# UMN_HASP_2015_GPS-IMU_Board.net
KiCad netlist of a schematic drawn in EAGLE
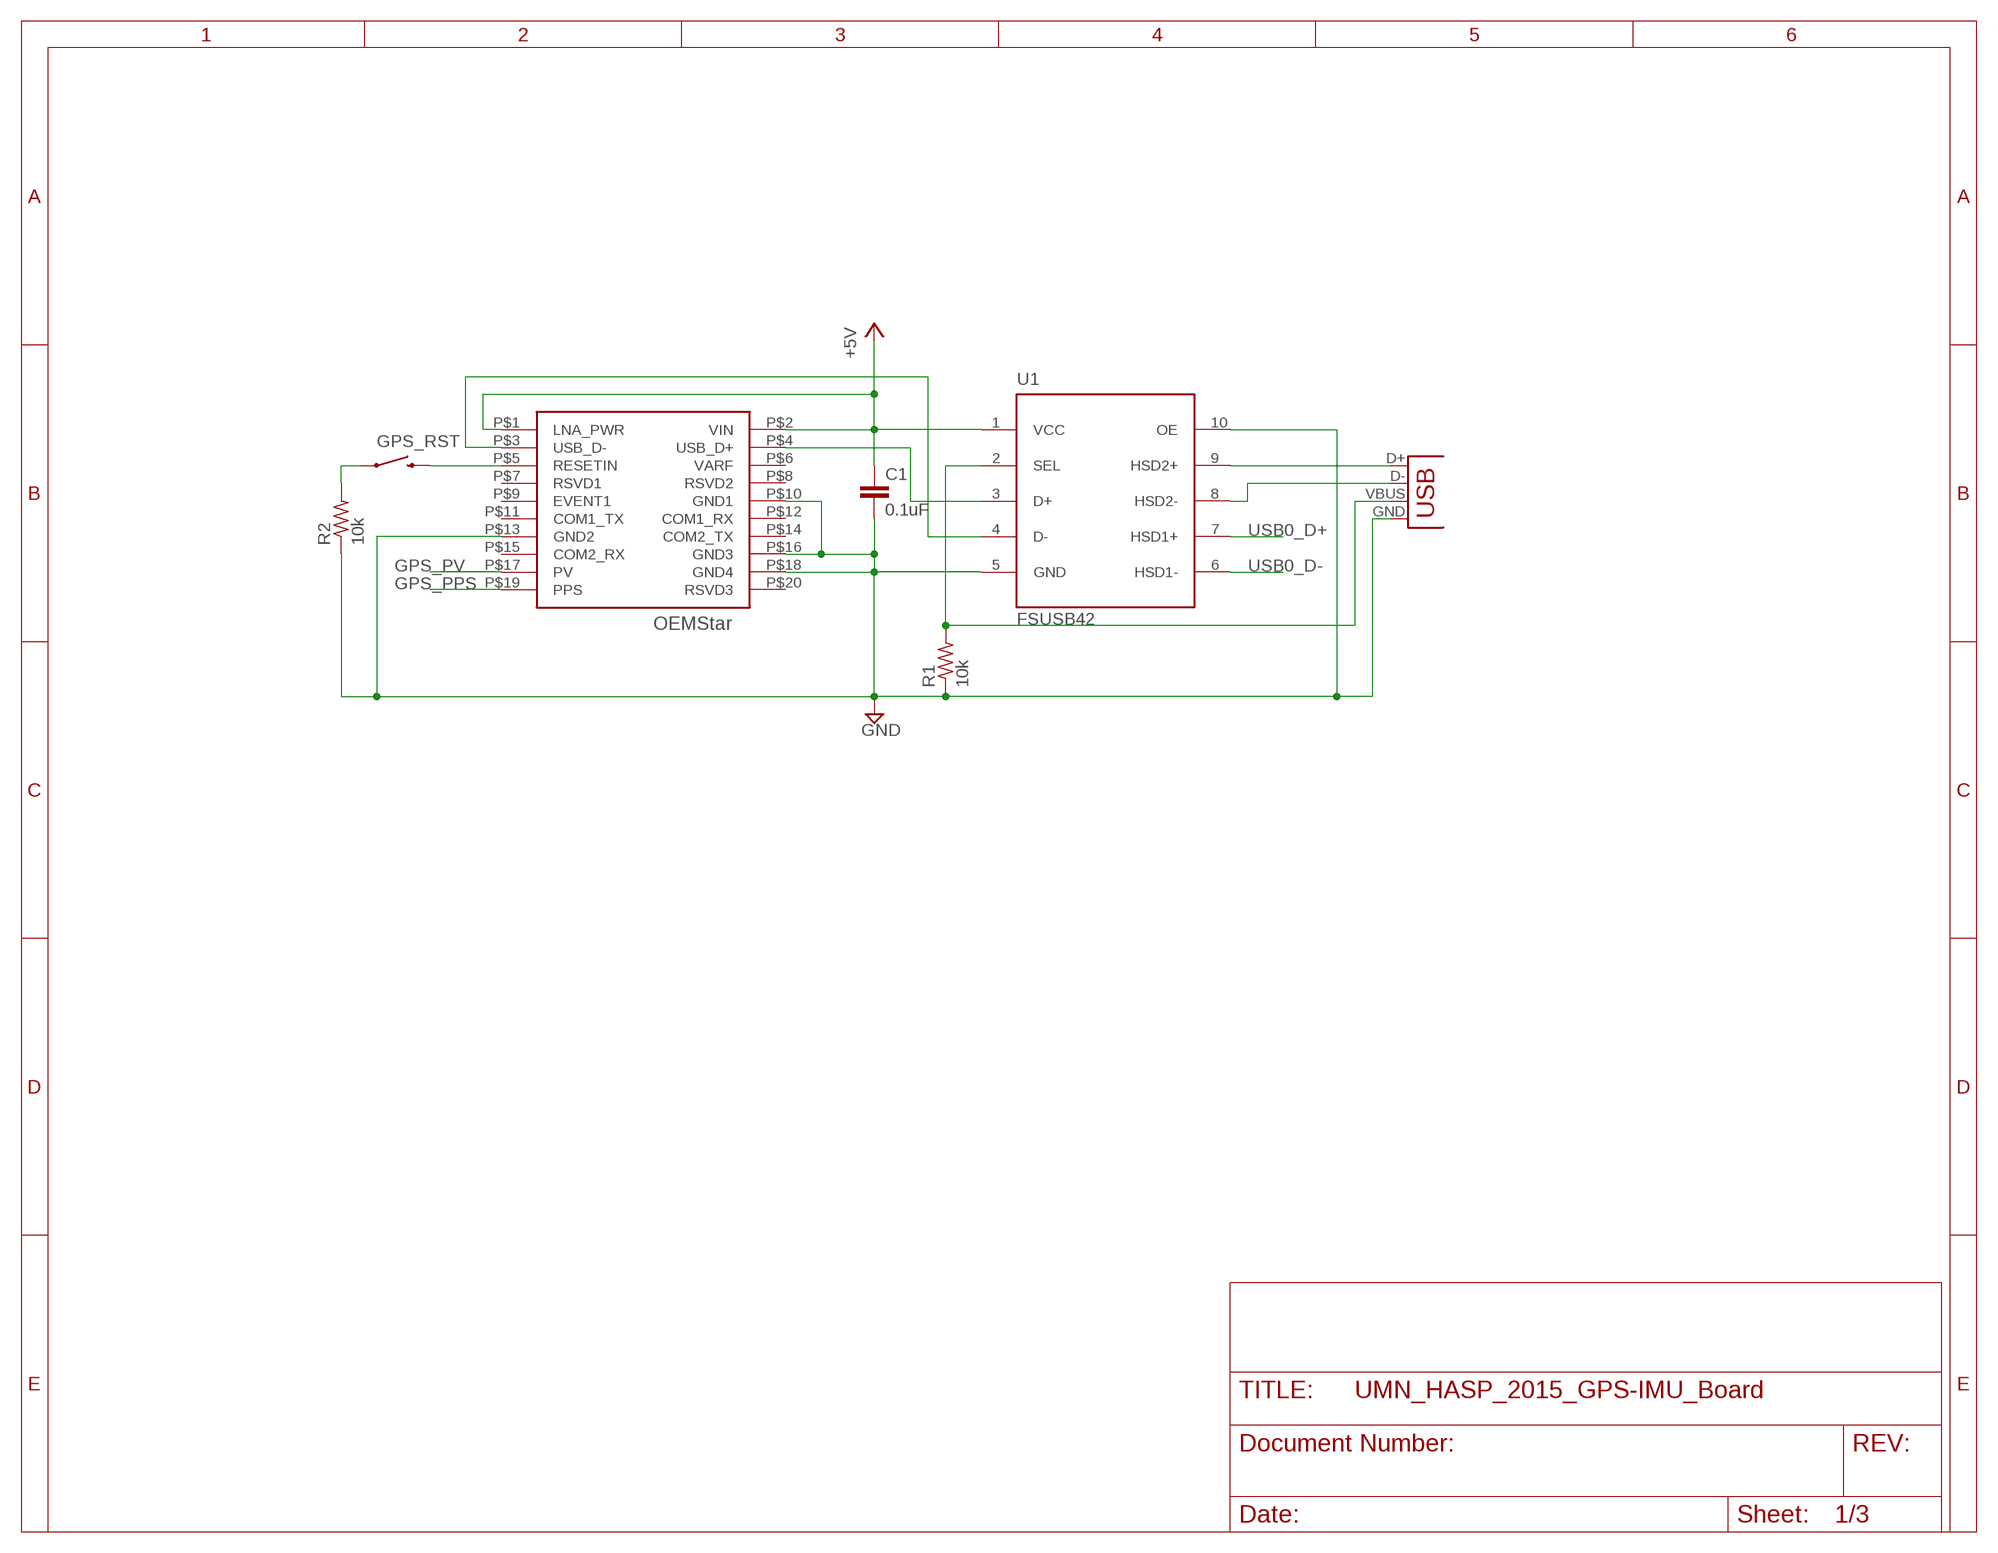
[diagram p0: schematic, sheet 1]
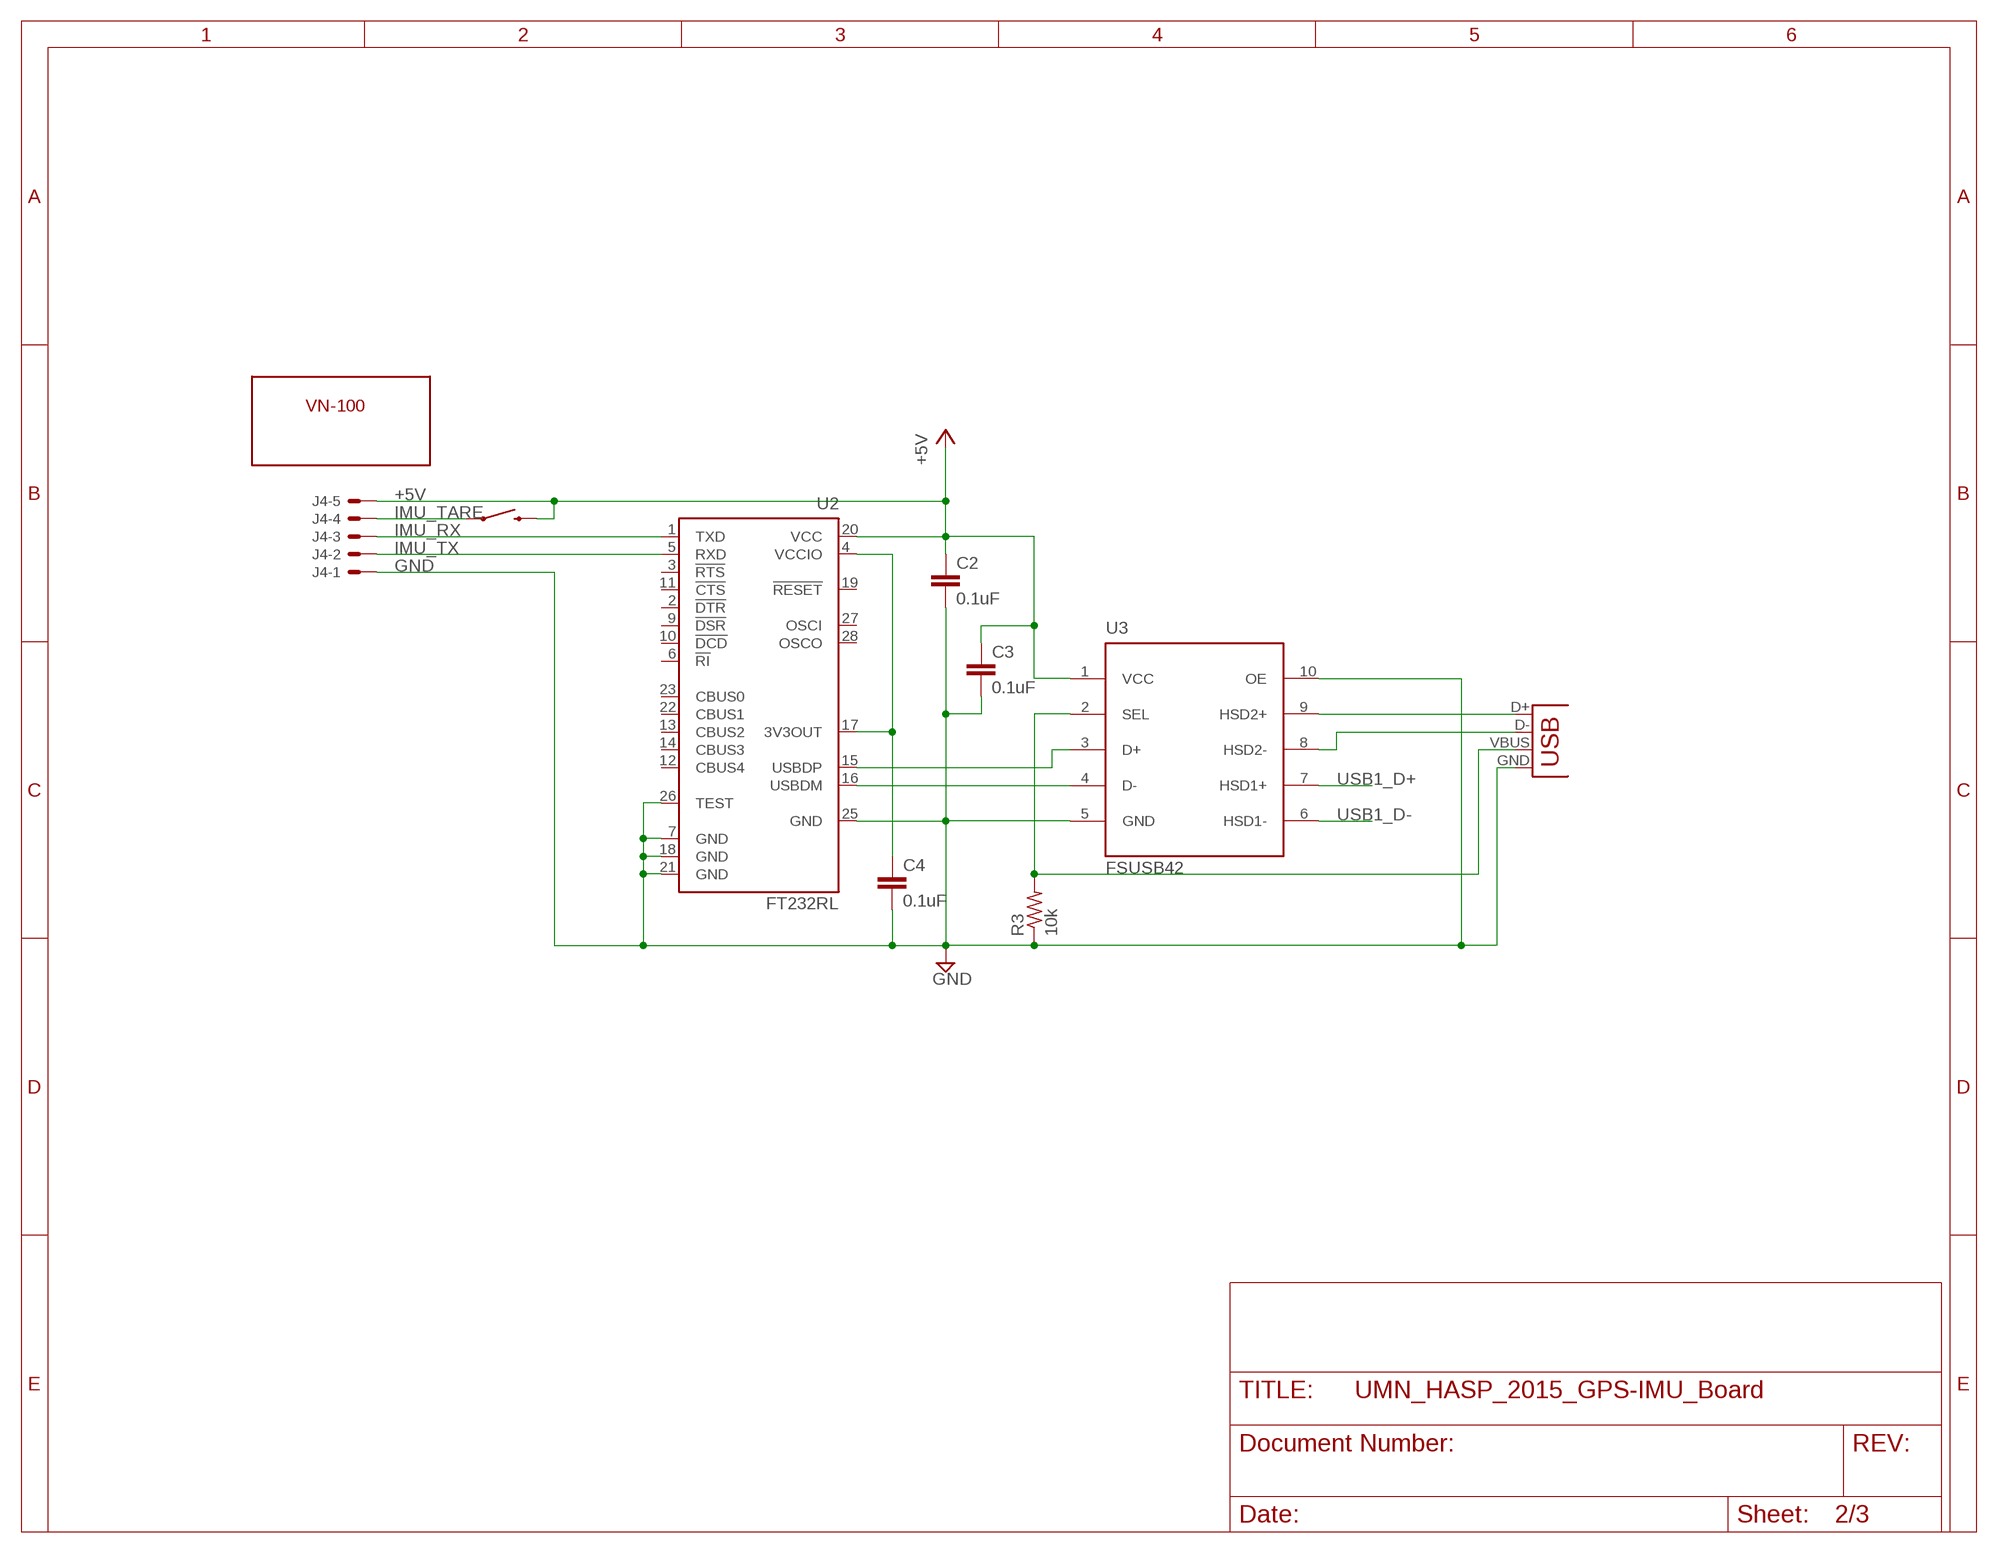
[diagram p1: schematic, sheet 2]
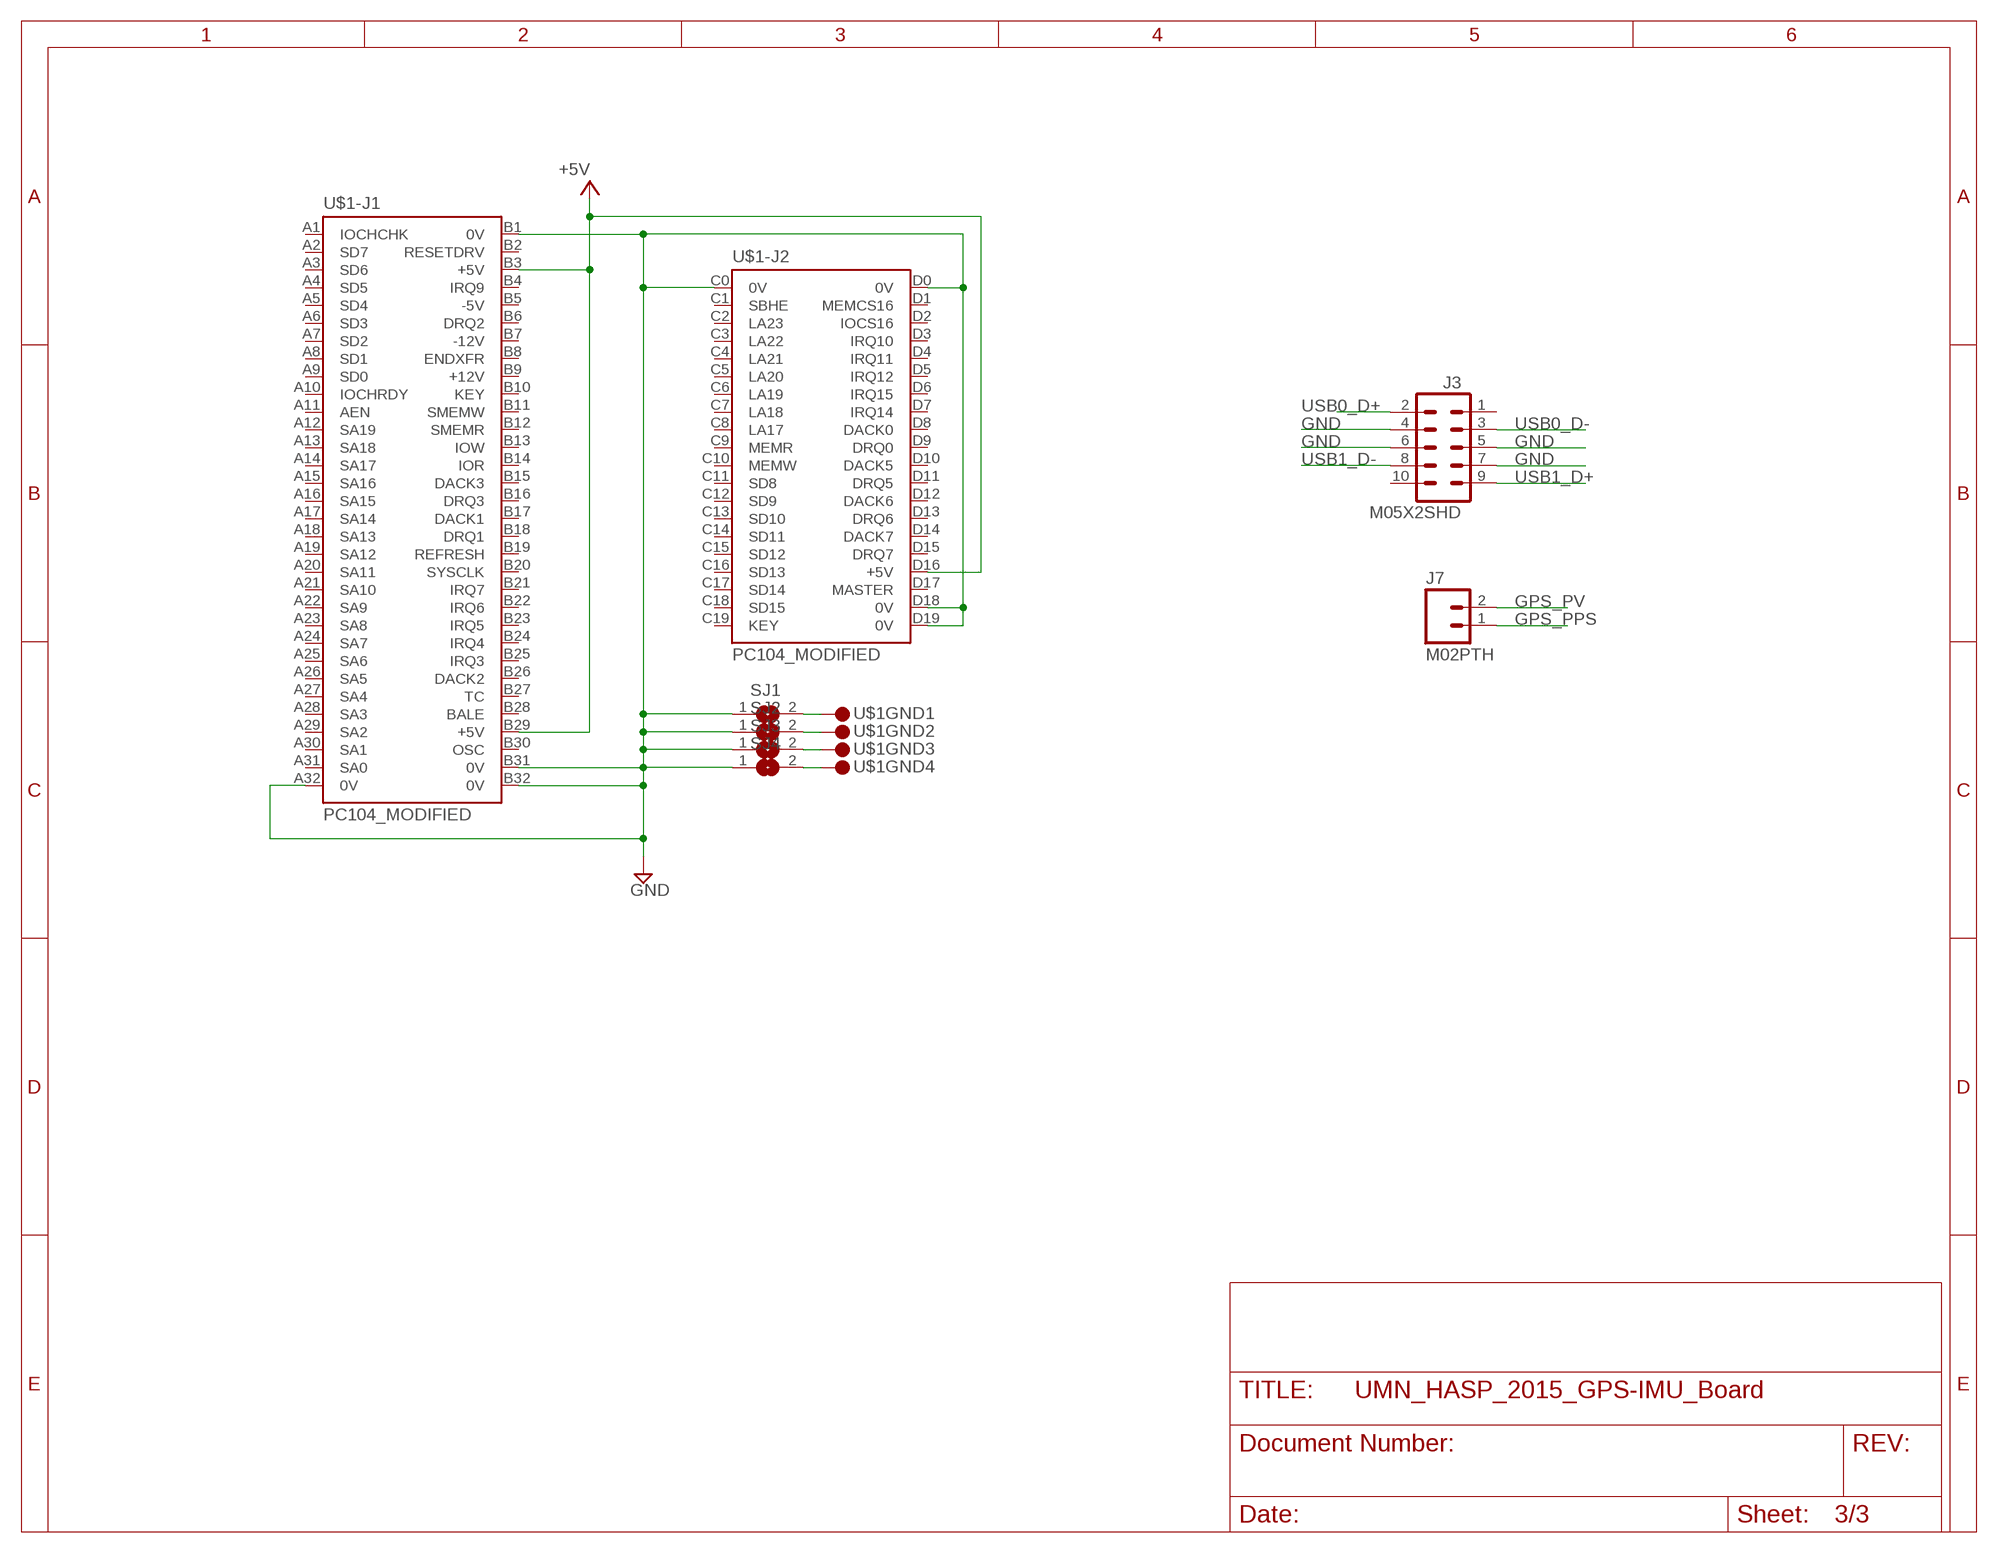
[diagram p2: schematic, sheet 3]

(export (version "E")
  (design (tool "Eeschema 10.0.6"))
  (components
    (comp (ref "J3")
      (value "M05X2SHD")
      (footprint "eagle-import:2X5-SHROUDED")
      (libsource (lib "eagle-import") (part "M05X2SHD"))
    )
    (comp (ref "J7")
      (value "M02PTH")
      (footprint "eagle-import:1X02")
      (libsource (lib "eagle-import") (part "M02PTH"))
    )
    (comp (ref "SJ1") (value "SJ") (footprint "eagle-import:SJ") (libsource (lib "eagle-import") (part "SJ")))
    (comp (ref "SJ2") (value "SJ") (footprint "eagle-import:SJ") (libsource (lib "eagle-import") (part "SJ")))
    (comp (ref "SJ3") (value "SJ") (footprint "eagle-import:SJ") (libsource (lib "eagle-import") (part "SJ")))
    (comp (ref "SJ4") (value "SJ") (footprint "eagle-import:SJ") (libsource (lib "eagle-import") (part "SJ")))
    (comp (ref "U$1")
      (value "PC104_MODIFIED")
      (footprint "eagle-import:PC104_MODIFIED")
      (libsource (lib "eagle-import") (part "PC104_MODIFIED"))
    )
    (comp (ref "C2")
      (value "0.1uF")
      (footprint "eagle-import:C1206K")
      (libsource (lib "eagle-import") (part "C-EUC1206K"))
    )
    (comp (ref "C3")
      (value "0.1uF")
      (footprint "eagle-import:C1206K")
      (libsource (lib "eagle-import") (part "C-EUC1206K"))
    )
    (comp (ref "C4")
      (value "0.1uF")
      (footprint "eagle-import:C1206K")
      (libsource (lib "eagle-import") (part "C-EUC1206K"))
    )
    (comp (ref "IMU_TARE")
      (value "SWITCH-MOMENTARY-2PTH")
      (footprint "eagle-import:TACTILE-PTH")
      (libsource (lib "eagle-import") (part "SWITCH-MOMENTARY-2PTH"))
    )
    (comp (ref "J4")
      (value "C-GRID-05-70553")
      (footprint "eagle-import:70553-05")
      (libsource (lib "eagle-import") (part "C-GRID-05-70553"))
    )
    (comp (ref "J5")
      (value "USB-B")
      (footprint "eagle-import:USB-B-PTH")
      (libsource (lib "eagle-import") (part "USBPTH"))
    )
    (comp (ref "R3")
      (value "10k")
      (footprint "eagle-import:R1206")
      (libsource (lib "eagle-import") (part "R-US_R1206"))
    )
    (comp (ref "U$3")
      (value "VN-100")
      (footprint "eagle-import:VN-100")
      (libsource (lib "eagle-import") (part "VN-100"))
    )
    (comp (ref "U2")
      (value "FT232RL")
      (footprint "eagle-import:SSOP28")
      (libsource (lib "eagle-import") (part "FT232RL"))
    )
    (comp (ref "U3")
      (value "FSUSB42")
      (footprint "eagle-import:MSOP10")
      (libsource (lib "eagle-import") (part "FSUSB42"))
    )
    (comp (ref "C1")
      (value "0.1uF")
      (footprint "eagle-import:C1206K")
      (libsource (lib "eagle-import") (part "C-EUC1206K"))
    )
    (comp (ref "GPS_RST")
      (value "SWITCH-MOMENTARY-2PTH")
      (footprint "eagle-import:TACTILE-PTH")
      (libsource (lib "eagle-import") (part "SWITCH-MOMENTARY-2PTH"))
    )
    (comp (ref "J6")
      (value "USB-B")
      (footprint "eagle-import:USB-B-PTH")
      (libsource (lib "eagle-import") (part "USBPTH"))
    )
    (comp (ref "R1")
      (value "10k")
      (footprint "eagle-import:R1206")
      (libsource (lib "eagle-import") (part "R-US_R1206"))
    )
    (comp (ref "R2")
      (value "10k")
      (footprint "eagle-import:R1206")
      (libsource (lib "eagle-import") (part "R-US_R1206"))
    )
    (comp (ref "U$2")
      (value "OEMSTAR")
      (footprint "eagle-import:OEMSTAR")
      (libsource (lib "eagle-import") (part "OEMSTAR"))
    )
    (comp (ref "U1")
      (value "FSUSB42")
      (footprint "eagle-import:MSOP10")
      (libsource (lib "eagle-import") (part "FSUSB42"))
    )
  )
  (nets
    (net (code "1") (name "+5V") (class "Default")
      (node (ref "C1") (pin "1") (pinfunction "1_1") (pintype "passive"))
      (node (ref "C2") (pin "1") (pinfunction "1_1") (pintype "passive"))
      (node (ref "C3") (pin "1") (pinfunction "1_1") (pintype "passive"))
      (node (ref "IMU_TARE") (pin "3") (pinfunction "2_3") (pintype "passive"))
      (node (ref "J4") (pin "5") (pinfunction "S_5") (pintype "passive"))
      (node (ref "U$1") (pin "B29") (pinfunction "+5V_B29") (pintype "passive"))
      (node (ref "U$1") (pin "B3") (pinfunction "+5V_B3") (pintype "passive"))
      (node (ref "U$1") (pin "D16") (pinfunction "+5V_D16") (pintype "passive"))
      (node (ref "U$2") (pin "P$1") (pinfunction "LNA_PWR_P$1") (pintype "bidirectional"))
      (node (ref "U$2") (pin "P$2") (pinfunction "VIN_P$2") (pintype "bidirectional"))
      (node (ref "U1") (pin "1") (pinfunction "VCC_1") (pintype "power_in"))
      (node (ref "U2") (pin "20") (pinfunction "VCC_20") (pintype "power_in"))
      (node (ref "U3") (pin "1") (pinfunction "VCC_1") (pintype "power_in"))
    )
    (net (code "2") (name "GND") (class "Default")
      (node (ref "C1") (pin "2") (pinfunction "2_2") (pintype "passive"))
      (node (ref "C2") (pin "2") (pinfunction "2_2") (pintype "passive"))
      (node (ref "C3") (pin "2") (pinfunction "2_2") (pintype "passive"))
      (node (ref "C4") (pin "2") (pinfunction "2_2") (pintype "passive"))
      (node (ref "J3") (pin "4") (pinfunction "4_4") (pintype "passive"))
      (node (ref "J3") (pin "5") (pinfunction "5_5") (pintype "passive"))
      (node (ref "J3") (pin "6") (pinfunction "6_6") (pintype "passive"))
      (node (ref "J3") (pin "7") (pinfunction "7_7") (pintype "passive"))
      (node (ref "J4") (pin "1") (pinfunction "S_1") (pintype "passive"))
      (node (ref "J5") (pin "GND") (pinfunction "GND_GND") (pintype "bidirectional"))
      (node (ref "J6") (pin "GND") (pinfunction "GND_GND") (pintype "bidirectional"))
      (node (ref "R1") (pin "1") (pinfunction "1_1") (pintype "passive"))
      (node (ref "R2") (pin "1") (pinfunction "1_1") (pintype "passive"))
      (node (ref "R3") (pin "1") (pinfunction "1_1") (pintype "passive"))
      (node (ref "SJ1") (pin "1") (pinfunction "1_1") (pintype "passive"))
      (node (ref "SJ2") (pin "1") (pinfunction "1_1") (pintype "passive"))
      (node (ref "SJ3") (pin "1") (pinfunction "1_1") (pintype "passive"))
      (node (ref "SJ4") (pin "1") (pinfunction "1_1") (pintype "passive"))
      (node (ref "U$1") (pin "A32") (pinfunction "0V_A32") (pintype "passive"))
      (node (ref "U$1") (pin "B1") (pinfunction "0V_B1") (pintype "passive"))
      (node (ref "U$1") (pin "B31") (pinfunction "0V_B31") (pintype "passive"))
      (node (ref "U$1") (pin "B32") (pinfunction "0V_B32") (pintype "passive"))
      (node (ref "U$1") (pin "C0") (pinfunction "0V_C0") (pintype "passive"))
      (node (ref "U$1") (pin "D0") (pinfunction "0V_D0") (pintype "passive"))
      (node (ref "U$1") (pin "D18") (pinfunction "0V_D18") (pintype "passive"))
      (node (ref "U$1") (pin "D19") (pinfunction "0V_D19") (pintype "passive"))
      (node (ref "U$2") (pin "P$10") (pinfunction "GND1_P$10") (pintype "bidirectional"))
      (node (ref "U$2") (pin "P$13") (pinfunction "GND2_P$13") (pintype "bidirectional"))
      (node (ref "U$2") (pin "P$16") (pinfunction "GND3_P$16") (pintype "bidirectional"))
      (node (ref "U$2") (pin "P$18") (pinfunction "GND4_P$18") (pintype "bidirectional"))
      (node (ref "U1") (pin "10") (pinfunction "OE_10") (pintype "input"))
      (node (ref "U1") (pin "5") (pinfunction "GND_5") (pintype "power_in"))
      (node (ref "U2") (pin "18") (pinfunction "GND_18") (pintype "power_in"))
      (node (ref "U2") (pin "21") (pinfunction "GND_21") (pintype "power_in"))
      (node (ref "U2") (pin "25") (pinfunction "GND_25") (pintype "power_in"))
      (node (ref "U2") (pin "26") (pinfunction "TEST_26") (pintype "input"))
      (node (ref "U2") (pin "7") (pinfunction "GND_7") (pintype "power_in"))
      (node (ref "U3") (pin "10") (pinfunction "OE_10") (pintype "input"))
      (node (ref "U3") (pin "5") (pinfunction "GND_5") (pintype "power_in"))
    )
    (net (code "3") (name "GPS_PPS") (class "Default")
      (node (ref "J7") (pin "1") (pinfunction "1_1") (pintype "passive"))
      (node (ref "U$2") (pin "P$19") (pinfunction "PPS_P$19") (pintype "bidirectional"))
    )
    (net (code "4") (name "GPS_PV") (class "Default")
      (node (ref "J7") (pin "2") (pinfunction "2_2") (pintype "passive"))
      (node (ref "U$2") (pin "P$17") (pinfunction "PV_P$17") (pintype "bidirectional"))
    )
    (net (code "5") (name "IMU_RX") (class "Default")
      (node (ref "J4") (pin "3") (pinfunction "S_3") (pintype "passive"))
      (node (ref "U2") (pin "1") (pinfunction "TXD_1") (pintype "output"))
    )
    (net (code "6") (name "IMU_TARE") (class "Default")
      (node (ref "IMU_TARE") (pin "1") (pinfunction "1_1") (pintype "passive"))
      (node (ref "J4") (pin "4") (pinfunction "S_4") (pintype "passive"))
    )
    (net (code "7") (name "IMU_TX") (class "Default")
      (node (ref "J4") (pin "2") (pinfunction "S_2") (pintype "passive"))
      (node (ref "U2") (pin "5") (pinfunction "RXD_5") (pintype "input"))
    )
    (net (code "8") (name "Net-(GPS_RST-2)") (class "Default")
      (node (ref "GPS_RST") (pin "3") (pinfunction "2_3") (pintype "passive"))
      (node (ref "U$2") (pin "P$5") (pinfunction "RESETIN_P$5") (pintype "bidirectional"))
    )
    (net (code "9") (name "Net-(GPS_RST-Pad1)") (class "Default")
      (node (ref "GPS_RST") (pin "1") (pinfunction "1_1") (pintype "passive"))
      (node (ref "R2") (pin "2") (pinfunction "2_2") (pintype "passive"))
    )
    (net (code "10") (name "Net-(U$1C-1)") (class "Default")
      (node (ref "SJ1") (pin "2") (pinfunction "2_2") (pintype "passive"))
      (node (ref "U$1") (pin "GND@1") (pinfunction "1_GND@1") (pintype "passive"))
    )
    (net (code "11") (name "Net-(U$1D-1)") (class "Default")
      (node (ref "SJ2") (pin "2") (pinfunction "2_2") (pintype "passive"))
      (node (ref "U$1") (pin "GND@2") (pinfunction "1_GND@2") (pintype "passive"))
    )
    (net (code "12") (name "Net-(U$1E-1)") (class "Default")
      (node (ref "SJ3") (pin "2") (pinfunction "2_2") (pintype "passive"))
      (node (ref "U$1") (pin "GND@3") (pinfunction "1_GND@3") (pintype "passive"))
    )
    (net (code "13") (name "Net-(U$1F-1)") (class "Default")
      (node (ref "SJ4") (pin "2") (pinfunction "2_2") (pintype "passive"))
      (node (ref "U$1") (pin "GND@4") (pinfunction "1_GND@4") (pintype "passive"))
    )
    (net (code "14") (name "Net-(U$2-USB_D+)") (class "Default")
      (node (ref "U$2") (pin "P$4") (pinfunction "USB_D+_P$4") (pintype "bidirectional"))
      (node (ref "U1") (pin "3") (pinfunction "D+_3") (pintype "bidirectional"))
    )
    (net (code "15") (name "Net-(U$2-USB_D-)") (class "Default")
      (node (ref "U$2") (pin "P$3") (pinfunction "USB_D-_P$3") (pintype "bidirectional"))
      (node (ref "U1") (pin "4") (pinfunction "D-_4") (pintype "bidirectional"))
    )
    (net (code "16") (name "Net-(U1-HSD2+)") (class "Default")
      (node (ref "J6") (pin "D+") (pinfunction "D+_D+") (pintype "bidirectional"))
      (node (ref "U1") (pin "9") (pinfunction "HSD2+_9") (pintype "bidirectional"))
    )
    (net (code "17") (name "Net-(U1-HSD2-)") (class "Default")
      (node (ref "J6") (pin "D-") (pinfunction "D-_D-") (pintype "bidirectional"))
      (node (ref "U1") (pin "8") (pinfunction "HSD2-_8") (pintype "bidirectional"))
    )
    (net (code "18") (name "Net-(U1-SEL)") (class "Default")
      (node (ref "J6") (pin "VBUS") (pinfunction "VBUS_VBUS") (pintype "bidirectional"))
      (node (ref "R1") (pin "2") (pinfunction "2_2") (pintype "passive"))
      (node (ref "U1") (pin "2") (pinfunction "SEL_2") (pintype "input"))
    )
    (net (code "19") (name "Net-(U2-3V3OUT)") (class "Default")
      (node (ref "C4") (pin "1") (pinfunction "1_1") (pintype "passive"))
      (node (ref "U2") (pin "17") (pinfunction "3V3OUT_17") (pintype "output"))
      (node (ref "U2") (pin "4") (pinfunction "VCCIO_4") (pintype "power_in"))
    )
    (net (code "20") (name "Net-(U2-USBDM)") (class "Default")
      (node (ref "U2") (pin "16") (pinfunction "USBDM_16") (pintype "bidirectional"))
      (node (ref "U3") (pin "4") (pinfunction "D-_4") (pintype "bidirectional"))
    )
    (net (code "21") (name "Net-(U2-USBDP)") (class "Default")
      (node (ref "U2") (pin "15") (pinfunction "USBDP_15") (pintype "bidirectional"))
      (node (ref "U3") (pin "3") (pinfunction "D+_3") (pintype "bidirectional"))
    )
    (net (code "22") (name "Net-(U3-HSD2+)") (class "Default")
      (node (ref "J5") (pin "D+") (pinfunction "D+_D+") (pintype "bidirectional"))
      (node (ref "U3") (pin "9") (pinfunction "HSD2+_9") (pintype "bidirectional"))
    )
    (net (code "23") (name "Net-(U3-HSD2-)") (class "Default")
      (node (ref "J5") (pin "D-") (pinfunction "D-_D-") (pintype "bidirectional"))
      (node (ref "U3") (pin "8") (pinfunction "HSD2-_8") (pintype "bidirectional"))
    )
    (net (code "24") (name "Net-(U3-SEL)") (class "Default")
      (node (ref "J5") (pin "VBUS") (pinfunction "VBUS_VBUS") (pintype "bidirectional"))
      (node (ref "R3") (pin "2") (pinfunction "2_2") (pintype "passive"))
      (node (ref "U3") (pin "2") (pinfunction "SEL_2") (pintype "input"))
    )
    (net (code "25") (name "USB0_D+") (class "Default")
      (node (ref "J3") (pin "2") (pinfunction "2_2") (pintype "passive"))
      (node (ref "U1") (pin "7") (pinfunction "HSD1+_7") (pintype "bidirectional"))
    )
    (net (code "26") (name "USB0_D-") (class "Default")
      (node (ref "J3") (pin "3") (pinfunction "3_3") (pintype "passive"))
      (node (ref "U1") (pin "6") (pinfunction "HSD1-_6") (pintype "bidirectional"))
    )
    (net (code "27") (name "USB1_D+") (class "Default")
      (node (ref "J3") (pin "9") (pinfunction "9_9") (pintype "passive"))
      (node (ref "U3") (pin "7") (pinfunction "HSD1+_7") (pintype "bidirectional"))
    )
    (net (code "28") (name "USB1_D-") (class "Default")
      (node (ref "J3") (pin "8") (pinfunction "8_8") (pintype "passive"))
      (node (ref "U3") (pin "6") (pinfunction "HSD1-_6") (pintype "bidirectional"))
    )
    (net (code "29") (name "unconnected-(J3-Pad1)") (class "Default")
      (node (ref "J3") (pin "1") (pinfunction "1_1") (pintype "passive"))
    )
    (net (code "30") (name "unconnected-(J3-Pad10)") (class "Default")
      (node (ref "J3") (pin "10") (pinfunction "10_10") (pintype "passive"))
    )
    (net (code "31") (name "unconnected-(U$1A-+12V-PadB9)") (class "Default")
      (node (ref "U$1") (pin "B9") (pinfunction "+12V_B9") (pintype "passive"))
    )
    (net (code "32") (name "unconnected-(U$1A--5V-PadB5)") (class "Default")
      (node (ref "U$1") (pin "B5") (pinfunction "-5V_B5") (pintype "passive"))
    )
    (net (code "33") (name "unconnected-(U$1A--12V-PadB7)") (class "Default")
      (node (ref "U$1") (pin "B7") (pinfunction "-12V_B7") (pintype "passive"))
    )
    (net (code "34") (name "unconnected-(U$1A-AEN-PadA11)") (class "Default")
      (node (ref "U$1") (pin "A11") (pinfunction "AEN_A11") (pintype "passive"))
    )
    (net (code "35") (name "unconnected-(U$1A-BALE-PadB28)") (class "Default")
      (node (ref "U$1") (pin "B28") (pinfunction "BALE_B28") (pintype "passive"))
    )
    (net (code "36") (name "unconnected-(U$1A-DACK1-PadB17)") (class "Default")
      (node (ref "U$1") (pin "B17") (pinfunction "DACK1_B17") (pintype "passive"))
    )
    (net (code "37") (name "unconnected-(U$1A-DACK2-PadB26)") (class "Default")
      (node (ref "U$1") (pin "B26") (pinfunction "DACK2_B26") (pintype "passive"))
    )
    (net (code "38") (name "unconnected-(U$1A-DACK3-PadB15)") (class "Default")
      (node (ref "U$1") (pin "B15") (pinfunction "DACK3_B15") (pintype "passive"))
    )
    (net (code "39") (name "unconnected-(U$1A-DRQ1-PadB18)") (class "Default")
      (node (ref "U$1") (pin "B18") (pinfunction "DRQ1_B18") (pintype "passive"))
    )
    (net (code "40") (name "unconnected-(U$1A-DRQ2-PadB6)") (class "Default")
      (node (ref "U$1") (pin "B6") (pinfunction "DRQ2_B6") (pintype "passive"))
    )
    (net (code "41") (name "unconnected-(U$1A-DRQ3-PadB16)") (class "Default")
      (node (ref "U$1") (pin "B16") (pinfunction "DRQ3_B16") (pintype "passive"))
    )
    (net (code "42") (name "unconnected-(U$1A-ENDXFR-PadB8)") (class "Default")
      (node (ref "U$1") (pin "B8") (pinfunction "ENDXFR_B8") (pintype "passive"))
    )
    (net (code "43") (name "unconnected-(U$1A-IOCHCHK-PadA1)") (class "Default")
      (node (ref "U$1") (pin "A1") (pinfunction "IOCHCHK_A1") (pintype "passive"))
    )
    (net (code "44") (name "unconnected-(U$1A-IOCHRDY-PadA10)") (class "Default")
      (node (ref "U$1") (pin "A10") (pinfunction "IOCHRDY_A10") (pintype "passive"))
    )
    (net (code "45") (name "unconnected-(U$1A-IOR-PadB14)") (class "Default")
      (node (ref "U$1") (pin "B14") (pinfunction "IOR_B14") (pintype "passive"))
    )
    (net (code "46") (name "unconnected-(U$1A-IOW-PadB13)") (class "Default")
      (node (ref "U$1") (pin "B13") (pinfunction "IOW_B13") (pintype "passive"))
    )
    (net (code "47") (name "unconnected-(U$1A-IRQ3-PadB25)") (class "Default")
      (node (ref "U$1") (pin "B25") (pinfunction "IRQ3_B25") (pintype "passive"))
    )
    (net (code "48") (name "unconnected-(U$1A-IRQ4-PadB24)") (class "Default")
      (node (ref "U$1") (pin "B24") (pinfunction "IRQ4_B24") (pintype "passive"))
    )
    (net (code "49") (name "unconnected-(U$1A-IRQ5-PadB23)") (class "Default")
      (node (ref "U$1") (pin "B23") (pinfunction "IRQ5_B23") (pintype "passive"))
    )
    (net (code "50") (name "unconnected-(U$1A-IRQ6-PadB22)") (class "Default")
      (node (ref "U$1") (pin "B22") (pinfunction "IRQ6_B22") (pintype "passive"))
    )
    (net (code "51") (name "unconnected-(U$1A-IRQ7-PadB21)") (class "Default")
      (node (ref "U$1") (pin "B21") (pinfunction "IRQ7_B21") (pintype "passive"))
    )
    (net (code "52") (name "unconnected-(U$1A-IRQ9-PadB4)") (class "Default")
      (node (ref "U$1") (pin "B4") (pinfunction "IRQ9_B4") (pintype "passive"))
    )
    (net (code "53") (name "unconnected-(U$1A-KEY-PadB10)") (class "Default")
      (node (ref "U$1") (pin "B10") (pinfunction "KEY_B10") (pintype "passive"))
    )
    (net (code "54") (name "unconnected-(U$1A-OSC-PadB30)") (class "Default")
      (node (ref "U$1") (pin "B30") (pinfunction "OSC_B30") (pintype "passive"))
    )
    (net (code "55") (name "unconnected-(U$1A-REFRESH-PadB19)") (class "Default")
      (node (ref "U$1") (pin "B19") (pinfunction "REFRESH_B19") (pintype "passive"))
    )
    (net (code "56") (name "unconnected-(U$1A-RESETDRV-PadB2)") (class "Default")
      (node (ref "U$1") (pin "B2") (pinfunction "RESETDRV_B2") (pintype "passive"))
    )
    (net (code "57") (name "unconnected-(U$1A-SA0-PadA31)") (class "Default")
      (node (ref "U$1") (pin "A31") (pinfunction "SA0_A31") (pintype "passive"))
    )
    (net (code "58") (name "unconnected-(U$1A-SA1-PadA30)") (class "Default")
      (node (ref "U$1") (pin "A30") (pinfunction "SA1_A30") (pintype "passive"))
    )
    (net (code "59") (name "unconnected-(U$1A-SA2-PadA29)") (class "Default")
      (node (ref "U$1") (pin "A29") (pinfunction "SA2_A29") (pintype "passive"))
    )
    (net (code "60") (name "unconnected-(U$1A-SA3-PadA28)") (class "Default")
      (node (ref "U$1") (pin "A28") (pinfunction "SA3_A28") (pintype "passive"))
    )
    (net (code "61") (name "unconnected-(U$1A-SA4-PadA27)") (class "Default")
      (node (ref "U$1") (pin "A27") (pinfunction "SA4_A27") (pintype "passive"))
    )
    (net (code "62") (name "unconnected-(U$1A-SA5-PadA26)") (class "Default")
      (node (ref "U$1") (pin "A26") (pinfunction "SA5_A26") (pintype "passive"))
    )
    (net (code "63") (name "unconnected-(U$1A-SA6-PadA25)") (class "Default")
      (node (ref "U$1") (pin "A25") (pinfunction "SA6_A25") (pintype "passive"))
    )
    (net (code "64") (name "unconnected-(U$1A-SA7-PadA24)") (class "Default")
      (node (ref "U$1") (pin "A24") (pinfunction "SA7_A24") (pintype "passive"))
    )
    (net (code "65") (name "unconnected-(U$1A-SA8-PadA23)") (class "Default")
      (node (ref "U$1") (pin "A23") (pinfunction "SA8_A23") (pintype "passive"))
    )
    (net (code "66") (name "unconnected-(U$1A-SA9-PadA22)") (class "Default")
      (node (ref "U$1") (pin "A22") (pinfunction "SA9_A22") (pintype "passive"))
    )
    (net (code "67") (name "unconnected-(U$1A-SA10-PadA21)") (class "Default")
      (node (ref "U$1") (pin "A21") (pinfunction "SA10_A21") (pintype "passive"))
    )
    (net (code "68") (name "unconnected-(U$1A-SA11-PadA20)") (class "Default")
      (node (ref "U$1") (pin "A20") (pinfunction "SA11_A20") (pintype "passive"))
    )
    (net (code "69") (name "unconnected-(U$1A-SA12-PadA19)") (class "Default")
      (node (ref "U$1") (pin "A19") (pinfunction "SA12_A19") (pintype "passive"))
    )
    (net (code "70") (name "unconnected-(U$1A-SA13-PadA18)") (class "Default")
      (node (ref "U$1") (pin "A18") (pinfunction "SA13_A18") (pintype "passive"))
    )
    (net (code "71") (name "unconnected-(U$1A-SA14-PadA17)") (class "Default")
      (node (ref "U$1") (pin "A17") (pinfunction "SA14_A17") (pintype "passive"))
    )
    (net (code "72") (name "unconnected-(U$1A-SA15-PadA16)") (class "Default")
      (node (ref "U$1") (pin "A16") (pinfunction "SA15_A16") (pintype "passive"))
    )
    (net (code "73") (name "unconnected-(U$1A-SA16-PadA15)") (class "Default")
      (node (ref "U$1") (pin "A15") (pinfunction "SA16_A15") (pintype "passive"))
    )
    (net (code "74") (name "unconnected-(U$1A-SA17-PadA14)") (class "Default")
      (node (ref "U$1") (pin "A14") (pinfunction "SA17_A14") (pintype "passive"))
    )
    (net (code "75") (name "unconnected-(U$1A-SA18-PadA13)") (class "Default")
      (node (ref "U$1") (pin "A13") (pinfunction "SA18_A13") (pintype "passive"))
    )
    (net (code "76") (name "unconnected-(U$1A-SA19-PadA12)") (class "Default")
      (node (ref "U$1") (pin "A12") (pinfunction "SA19_A12") (pintype "passive"))
    )
    (net (code "77") (name "unconnected-(U$1A-SD0-PadA9)") (class "Default")
      (node (ref "U$1") (pin "A9") (pinfunction "SD0_A9") (pintype "passive"))
    )
    (net (code "78") (name "unconnected-(U$1A-SD1-PadA8)") (class "Default")
      (node (ref "U$1") (pin "A8") (pinfunction "SD1_A8") (pintype "passive"))
    )
    (net (code "79") (name "unconnected-(U$1A-SD2-PadA7)") (class "Default")
      (node (ref "U$1") (pin "A7") (pinfunction "SD2_A7") (pintype "passive"))
    )
    (net (code "80") (name "unconnected-(U$1A-SD3-PadA6)") (class "Default")
      (node (ref "U$1") (pin "A6") (pinfunction "SD3_A6") (pintype "passive"))
    )
    (net (code "81") (name "unconnected-(U$1A-SD4-PadA5)") (class "Default")
      (node (ref "U$1") (pin "A5") (pinfunction "SD4_A5") (pintype "passive"))
    )
    (net (code "82") (name "unconnected-(U$1A-SD5-PadA4)") (class "Default")
      (node (ref "U$1") (pin "A4") (pinfunction "SD5_A4") (pintype "passive"))
    )
    (net (code "83") (name "unconnected-(U$1A-SD6-PadA3)") (class "Default")
      (node (ref "U$1") (pin "A3") (pinfunction "SD6_A3") (pintype "passive"))
    )
    (net (code "84") (name "unconnected-(U$1A-SD7-PadA2)") (class "Default")
      (node (ref "U$1") (pin "A2") (pinfunction "SD7_A2") (pintype "passive"))
    )
    (net (code "85") (name "unconnected-(U$1A-SMEMR-PadB12)") (class "Default")
      (node (ref "U$1") (pin "B12") (pinfunction "SMEMR_B12") (pintype "passive"))
    )
    (net (code "86") (name "unconnected-(U$1A-SMEMW-PadB11)") (class "Default")
      (node (ref "U$1") (pin "B11") (pinfunction "SMEMW_B11") (pintype "passive"))
    )
    (net (code "87") (name "unconnected-(U$1A-SYSCLK-PadB20)") (class "Default")
      (node (ref "U$1") (pin "B20") (pinfunction "SYSCLK_B20") (pintype "passive"))
    )
    (net (code "88") (name "unconnected-(U$1A-TC-PadB27)") (class "Default")
      (node (ref "U$1") (pin "B27") (pinfunction "TC_B27") (pintype "passive"))
    )
    (net (code "89") (name "unconnected-(U$1B-DACK0-PadD8)") (class "Default")
      (node (ref "U$1") (pin "D8") (pinfunction "DACK0_D8") (pintype "passive"))
    )
    (net (code "90") (name "unconnected-(U$1B-DACK5-PadD10)") (class "Default")
      (node (ref "U$1") (pin "D10") (pinfunction "DACK5_D10") (pintype "passive"))
    )
    (net (code "91") (name "unconnected-(U$1B-DACK6-PadD12)") (class "Default")
      (node (ref "U$1") (pin "D12") (pinfunction "DACK6_D12") (pintype "passive"))
    )
    (net (code "92") (name "unconnected-(U$1B-DACK7-PadD14)") (class "Default")
      (node (ref "U$1") (pin "D14") (pinfunction "DACK7_D14") (pintype "passive"))
    )
    (net (code "93") (name "unconnected-(U$1B-DRQ0-PadD9)") (class "Default")
      (node (ref "U$1") (pin "D9") (pinfunction "DRQ0_D9") (pintype "passive"))
    )
    (net (code "94") (name "unconnected-(U$1B-DRQ5-PadD11)") (class "Default")
      (node (ref "U$1") (pin "D11") (pinfunction "DRQ5_D11") (pintype "passive"))
    )
    (net (code "95") (name "unconnected-(U$1B-DRQ6-PadD13)") (class "Default")
      (node (ref "U$1") (pin "D13") (pinfunction "DRQ6_D13") (pintype "passive"))
    )
    (net (code "96") (name "unconnected-(U$1B-DRQ7-PadD15)") (class "Default")
      (node (ref "U$1") (pin "D15") (pinfunction "DRQ7_D15") (pintype "passive"))
    )
    (net (code "97") (name "unconnected-(U$1B-IOCS16-PadD2)") (class "Default")
      (node (ref "U$1") (pin "D2") (pinfunction "IOCS16_D2") (pintype "passive"))
    )
    (net (code "98") (name "unconnected-(U$1B-IRQ10-PadD3)") (class "Default")
      (node (ref "U$1") (pin "D3") (pinfunction "IRQ10_D3") (pintype "passive"))
    )
    (net (code "99") (name "unconnected-(U$1B-IRQ11-PadD4)") (class "Default")
      (node (ref "U$1") (pin "D4") (pinfunction "IRQ11_D4") (pintype "passive"))
    )
    (net (code "100") (name "unconnected-(U$1B-IRQ12-PadD5)") (class "Default")
      (node (ref "U$1") (pin "D5") (pinfunction "IRQ12_D5") (pintype "passive"))
    )
    (net (code "101") (name "unconnected-(U$1B-IRQ14-PadD7)") (class "Default")
      (node (ref "U$1") (pin "D7") (pinfunction "IRQ14_D7") (pintype "passive"))
    )
    (net (code "102") (name "unconnected-(U$1B-IRQ15-PadD6)") (class "Default")
      (node (ref "U$1") (pin "D6") (pinfunction "IRQ15_D6") (pintype "passive"))
    )
    (net (code "103") (name "unconnected-(U$1B-KEY-PadC19)") (class "Default")
      (node (ref "U$1") (pin "C19") (pinfunction "KEY_C19") (pintype "passive"))
    )
    (net (code "104") (name "unconnected-(U$1B-LA17-PadC8)") (class "Default")
      (node (ref "U$1") (pin "C8") (pinfunction "LA17_C8") (pintype "passive"))
    )
    (net (code "105") (name "unconnected-(U$1B-LA18-PadC7)") (class "Default")
      (node (ref "U$1") (pin "C7") (pinfunction "LA18_C7") (pintype "passive"))
    )
    (net (code "106") (name "unconnected-(U$1B-LA19-PadC6)") (class "Default")
      (node (ref "U$1") (pin "C6") (pinfunction "LA19_C6") (pintype "passive"))
    )
    (net (code "107") (name "unconnected-(U$1B-LA20-PadC5)") (class "Default")
      (node (ref "U$1") (pin "C5") (pinfunction "LA20_C5") (pintype "passive"))
    )
    (net (code "108") (name "unconnected-(U$1B-LA21-PadC4)") (class "Default")
      (node (ref "U$1") (pin "C4") (pinfunction "LA21_C4") (pintype "passive"))
    )
    (net (code "109") (name "unconnected-(U$1B-LA22-PadC3)") (class "Default")
      (node (ref "U$1") (pin "C3") (pinfunction "LA22_C3") (pintype "passive"))
    )
    (net (code "110") (name "unconnected-(U$1B-LA23-PadC2)") (class "Default")
      (node (ref "U$1") (pin "C2") (pinfunction "LA23_C2") (pintype "passive"))
    )
    (net (code "111") (name "unconnected-(U$1B-MASTER-PadD17)") (class "Default")
      (node (ref "U$1") (pin "D17") (pinfunction "MASTER_D17") (pintype "passive"))
    )
    (net (code "112") (name "unconnected-(U$1B-MEMCS16-PadD1)") (class "Default")
      (node (ref "U$1") (pin "D1") (pinfunction "MEMCS16_D1") (pintype "passive"))
    )
    (net (code "113") (name "unconnected-(U$1B-MEMR-PadC9)") (class "Default")
      (node (ref "U$1") (pin "C9") (pinfunction "MEMR_C9") (pintype "passive"))
    )
    (net (code "114") (name "unconnected-(U$1B-MEMW-PadC10)") (class "Default")
      (node (ref "U$1") (pin "C10") (pinfunction "MEMW_C10") (pintype "passive"))
    )
    (net (code "115") (name "unconnected-(U$1B-SBHE-PadC1)") (class "Default")
      (node (ref "U$1") (pin "C1") (pinfunction "SBHE_C1") (pintype "passive"))
    )
    (net (code "116") (name "unconnected-(U$1B-SD8-PadC11)") (class "Default")
      (node (ref "U$1") (pin "C11") (pinfunction "SD8_C11") (pintype "passive"))
    )
    (net (code "117") (name "unconnected-(U$1B-SD9-PadC12)") (class "Default")
      (node (ref "U$1") (pin "C12") (pinfunction "SD9_C12") (pintype "passive"))
    )
    (net (code "118") (name "unconnected-(U$1B-SD10-PadC13)") (class "Default")
      (node (ref "U$1") (pin "C13") (pinfunction "SD10_C13") (pintype "passive"))
    )
    (net (code "119") (name "unconnected-(U$1B-SD11-PadC14)") (class "Default")
      (node (ref "U$1") (pin "C14") (pinfunction "SD11_C14") (pintype "passive"))
    )
    (net (code "120") (name "unconnected-(U$1B-SD12-PadC15)") (class "Default")
      (node (ref "U$1") (pin "C15") (pinfunction "SD12_C15") (pintype "passive"))
    )
    (net (code "121") (name "unconnected-(U$1B-SD13-PadC16)") (class "Default")
      (node (ref "U$1") (pin "C16") (pinfunction "SD13_C16") (pintype "passive"))
    )
    (net (code "122") (name "unconnected-(U$1B-SD14-PadC17)") (class "Default")
      (node (ref "U$1") (pin "C17") (pinfunction "SD14_C17") (pintype "passive"))
    )
    (net (code "123") (name "unconnected-(U$1B-SD15-PadC18)") (class "Default")
      (node (ref "U$1") (pin "C18") (pinfunction "SD15_C18") (pintype "passive"))
    )
    (net (code "124") (name "unconnected-(U$2-COM1_RX-PadP$12)") (class "Default")
      (node (ref "U$2") (pin "P$12") (pinfunction "COM1_RX_P$12") (pintype "bidirectional"))
    )
    (net (code "125") (name "unconnected-(U$2-COM1_TX-PadP$11)") (class "Default")
      (node (ref "U$2") (pin "P$11") (pinfunction "COM1_TX_P$11") (pintype "bidirectional"))
    )
    (net (code "126") (name "unconnected-(U$2-COM2_RX-PadP$15)") (class "Default")
      (node (ref "U$2") (pin "P$15") (pinfunction "COM2_RX_P$15") (pintype "bidirectional"))
    )
    (net (code "127") (name "unconnected-(U$2-COM2_TX-PadP$14)") (class "Default")
      (node (ref "U$2") (pin "P$14") (pinfunction "COM2_TX_P$14") (pintype "bidirectional"))
    )
    (net (code "128") (name "unconnected-(U$2-EVENT1-PadP$9)") (class "Default")
      (node (ref "U$2") (pin "P$9") (pinfunction "EVENT1_P$9") (pintype "bidirectional"))
    )
    (net (code "129") (name "unconnected-(U$2-RSVD1-PadP$7)") (class "Default")
      (node (ref "U$2") (pin "P$7") (pinfunction "RSVD1_P$7") (pintype "no_connect"))
    )
    (net (code "130") (name "unconnected-(U$2-RSVD2-PadP$8)") (class "Default")
      (node (ref "U$2") (pin "P$8") (pinfunction "RSVD2_P$8") (pintype "no_connect"))
    )
    (net (code "131") (name "unconnected-(U$2-RSVD3-PadP$20)") (class "Default")
      (node (ref "U$2") (pin "P$20") (pinfunction "RSVD3_P$20") (pintype "no_connect"))
    )
    (net (code "132") (name "unconnected-(U$2-VARF-PadP$6)") (class "Default")
      (node (ref "U$2") (pin "P$6") (pinfunction "VARF_P$6") (pintype "bidirectional"))
    )
    (net (code "133") (name "unconnected-(U2-CBUS0-Pad23)") (class "Default")
      (node (ref "U2") (pin "23") (pinfunction "CBUS0_23") (pintype "bidirectional"))
    )
    (net (code "134") (name "unconnected-(U2-CBUS1-Pad22)") (class "Default")
      (node (ref "U2") (pin "22") (pinfunction "CBUS1_22") (pintype "bidirectional"))
    )
    (net (code "135") (name "unconnected-(U2-CBUS2-Pad13)") (class "Default")
      (node (ref "U2") (pin "13") (pinfunction "CBUS2_13") (pintype "bidirectional"))
    )
    (net (code "136") (name "unconnected-(U2-CBUS3-Pad14)") (class "Default")
      (node (ref "U2") (pin "14") (pinfunction "CBUS3_14") (pintype "bidirectional"))
    )
    (net (code "137") (name "unconnected-(U2-CBUS4-Pad12)") (class "Default")
      (node (ref "U2") (pin "12") (pinfunction "CBUS4_12") (pintype "bidirectional"))
    )
    (net (code "138") (name "unconnected-(U2-OSCI-Pad27)") (class "Default")
      (node (ref "U2") (pin "27") (pinfunction "OSCI_27") (pintype "input"))
    )
    (net (code "139") (name "unconnected-(U2-OSCO-Pad28)") (class "Default")
      (node (ref "U2") (pin "28") (pinfunction "OSCO_28") (pintype "output"))
    )
    (net (code "140") (name "unconnected-(U2-~{CTS}-Pad11)") (class "Default")
      (node (ref "U2") (pin "11") (pinfunction "~{CTS}_11") (pintype "input"))
    )
    (net (code "141") (name "unconnected-(U2-~{DCD}-Pad10)") (class "Default")
      (node (ref "U2") (pin "10") (pinfunction "~{DCD}_10") (pintype "input"))
    )
    (net (code "142") (name "unconnected-(U2-~{DSR}-Pad9)") (class "Default")
      (node (ref "U2") (pin "9") (pinfunction "~{DSR}_9") (pintype "input"))
    )
    (net (code "143") (name "unconnected-(U2-~{DTR}-Pad2)") (class "Default")
      (node (ref "U2") (pin "2") (pinfunction "~{DTR}_2") (pintype "output"))
    )
    (net (code "144") (name "unconnected-(U2-~{RESET}-Pad19)") (class "Default")
      (node (ref "U2") (pin "19") (pinfunction "~{RESET}_19") (pintype "input"))
    )
    (net (code "145") (name "unconnected-(U2-~{RI}-Pad6)") (class "Default")
      (node (ref "U2") (pin "6") (pinfunction "~{RI}_6") (pintype "input"))
    )
    (net (code "146") (name "unconnected-(U2-~{RTS}-Pad3)") (class "Default")
      (node (ref "U2") (pin "3") (pinfunction "~{RTS}_3") (pintype "output"))
    )
  )
)
